# Schematic.net
KiCad netlist of a schematic drawn in EAGLE
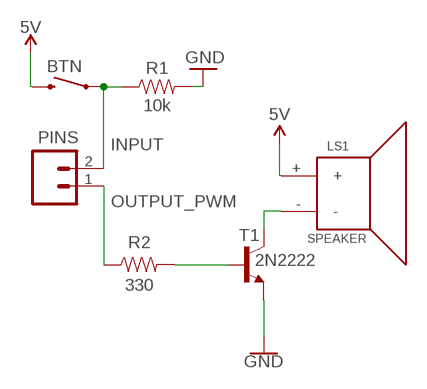
[diagram p0: schematic, sheet 1]

(export (version "E")
  (design (tool "Eeschema 10.0.6"))
  (components
    (comp (ref "BTN")
      (value "MOMENTARY-SWITCH-SPST-PTH-6.0MM")
      (footprint "eagle-import:TACTILE_SWITCH_PTH_6.0MM")
      (libsource (lib "eagle-import") (part "MOMENTARY-SWITCH-SPST-PTH-6.0MM"))
    )
    (comp (ref "LS1")
      (value "SPEAKER")
      (footprint "eagle-import:PCB_MOUNT_SPEAKER")
      (libsource (lib "eagle-import") (part "SPEAKER"))
    )
    (comp (ref "PINS")
      (value "CONN_02")
      (footprint "eagle-import:1X02")
      (libsource (lib "eagle-import") (part "CONN_02"))
    )
    (comp (ref "R1")
      (value "10k")
      (footprint "eagle-import:AXIAL-0.3")
      (libsource (lib "eagle-import") (part "10KOHM-HORIZ-1/4W-1%"))
    )
    (comp (ref "R2")
      (value "330")
      (footprint "eagle-import:AXIAL-0.3")
      (libsource (lib "eagle-import") (part "330OHM-HORIZ-1/10W-5%"))
    )
    (comp (ref "T1")
      (value "2N2222")
      (footprint "eagle-import:TO92-EBC-OVAL")
      (libsource (lib "eagle-import") (part "2N2222"))
    )
  )
  (nets
    (net (code "1") (name "/INPUT") (class "Default")
      (node (ref "BTN") (pin "1") (pinfunction "1_1") (pintype "passive"))
      (node (ref "PINS") (pin "2") (pinfunction "2_2") (pintype "passive"))
      (node (ref "R1") (pin "P$1") (pinfunction "1_P$1") (pintype "passive"))
    )
    (net (code "2") (name "/OUTPUT_PWM") (class "Default")
      (node (ref "PINS") (pin "1") (pinfunction "1_1") (pintype "passive"))
      (node (ref "R2") (pin "P$1") (pinfunction "1_P$1") (pintype "passive"))
    )
    (net (code "3") (name "5V") (class "Default")
      (node (ref "BTN") (pin "3") (pinfunction "2_3") (pintype "passive"))
      (node (ref "LS1") (pin "+") (pinfunction "+_+") (pintype "bidirectional"))
    )
    (net (code "4") (name "GND") (class "Default")
      (node (ref "R1") (pin "P$2") (pinfunction "2_P$2") (pintype "passive"))
      (node (ref "T1") (pin "E") (pinfunction "E_E") (pintype "passive"))
    )
    (net (code "5") (name "Net-(LS1-Pad-)") (class "Default")
      (node (ref "LS1") (pin "-") (pinfunction "-_-") (pintype "bidirectional"))
      (node (ref "T1") (pin "C") (pinfunction "C_C") (pintype "passive"))
    )
    (net (code "6") (name "Net-(R2-2)") (class "Default")
      (node (ref "R2") (pin "P$2") (pinfunction "2_P$2") (pintype "passive"))
      (node (ref "T1") (pin "B") (pinfunction "B_B") (pintype "passive"))
    )
  )
)
